# Connectors_ADC.net
KiCad netlist of a schematic drawn in Altium Designer
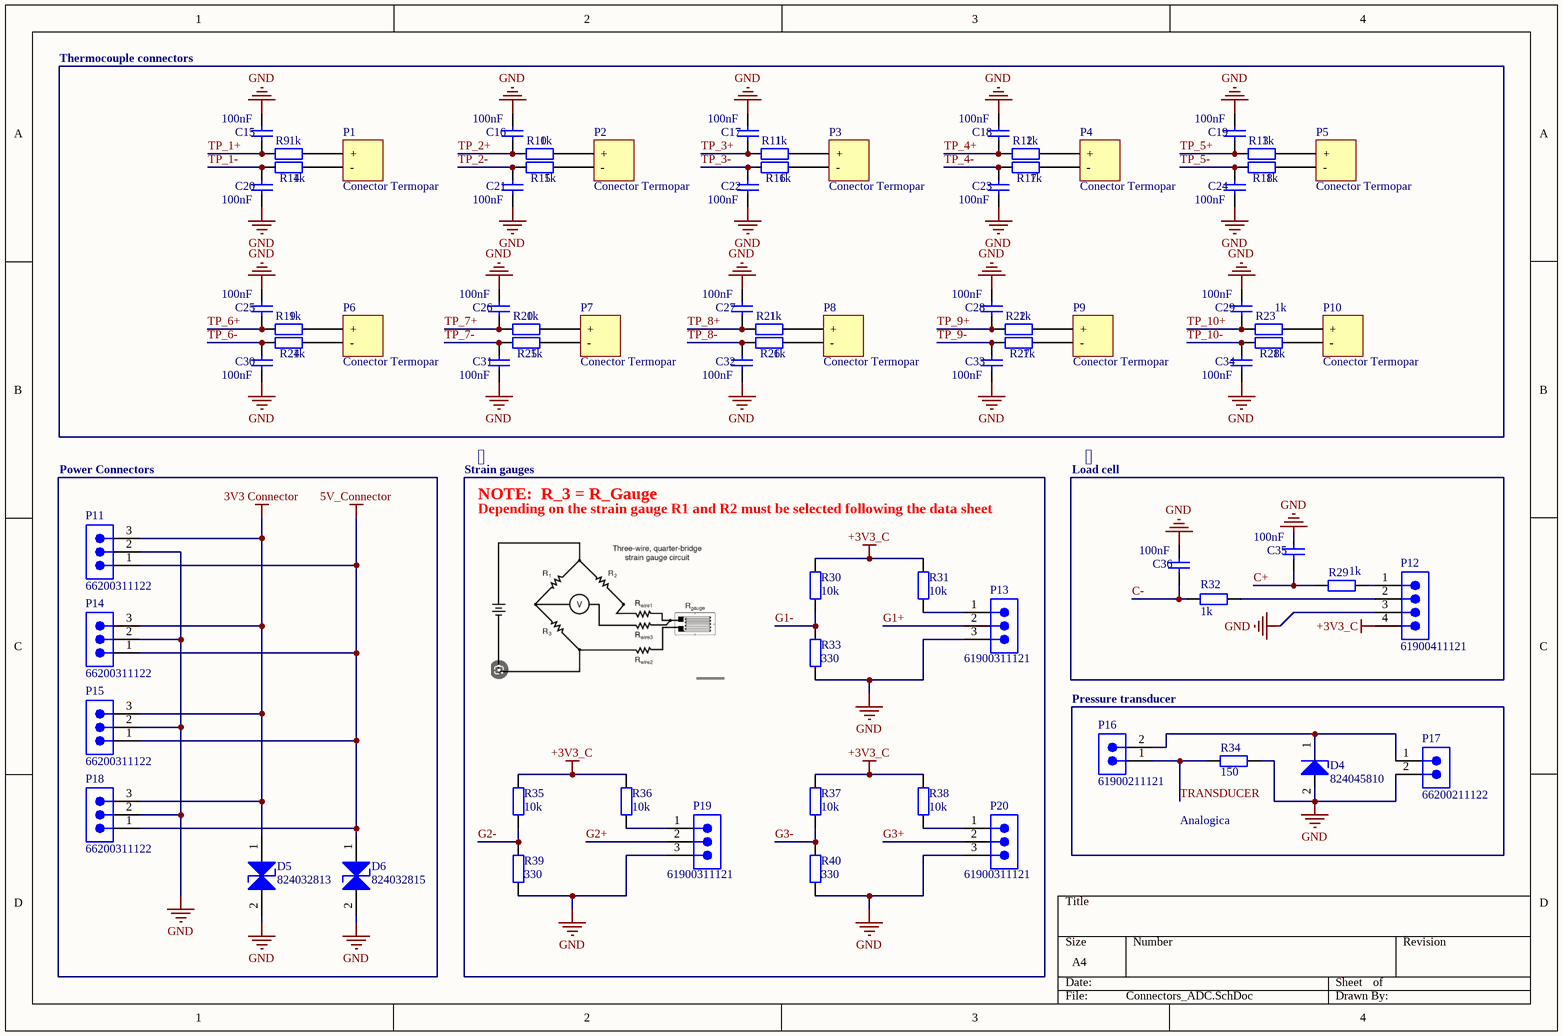
[diagram p0: Connectors_ADC.SchDoc]

(export (version "E")
  (design (tool "Eeschema 10.0.6"))
  (components
    (comp (ref "C15")
      (value "100nF")
      (footprint "WCAP-CSGP_0603_L1.6W0.8H0.8_Reflow")
      (description "WCAP-CSGP Multilayer Ceramic Chip Capacitor, General Purpose, size 0603, X7R, 100nF, 25VDC")
      (fields
        (field (name "MANUFACTURER") "Wurth Elektronik")
        (field (name "MANUFACTURER PART NUMBER") "885012206071")
      )
      (libsource (lib "LEEM UPM") (part "885012209047R"))
    )
    (comp (ref "C16")
      (value "100nF")
      (footprint "WCAP-CSGP_0603_L1.6W0.8H0.8_Reflow")
      (description "WCAP-CSGP Multilayer Ceramic Chip Capacitor, General Purpose, size 0603, X7R, 100nF, 25VDC")
      (fields
        (field (name "MANUFACTURER") "Wurth Elektronik")
        (field (name "MANUFACTURER PART NUMBER") "885012206071")
      )
      (libsource (lib "LEEM UPM") (part "885012209047R"))
    )
    (comp (ref "C17")
      (value "100nF")
      (footprint "WCAP-CSGP_0603_L1.6W0.8H0.8_Reflow")
      (description "WCAP-CSGP Multilayer Ceramic Chip Capacitor, General Purpose, size 0603, X7R, 100nF, 25VDC")
      (fields
        (field (name "MANUFACTURER") "Wurth Elektronik")
        (field (name "MANUFACTURER PART NUMBER") "885012206071")
      )
      (libsource (lib "LEEM UPM") (part "885012209047R"))
    )
    (comp (ref "C18")
      (value "100nF")
      (footprint "WCAP-CSGP_0603_L1.6W0.8H0.8_Reflow")
      (description "WCAP-CSGP Multilayer Ceramic Chip Capacitor, General Purpose, size 0603, X7R, 100nF, 25VDC")
      (fields
        (field (name "MANUFACTURER") "Wurth Elektronik")
        (field (name "MANUFACTURER PART NUMBER") "885012206071")
      )
      (libsource (lib "LEEM UPM") (part "885012209047R"))
    )
    (comp (ref "C19")
      (value "100nF")
      (footprint "WCAP-CSGP_0603_L1.6W0.8H0.8_Reflow")
      (description "WCAP-CSGP Multilayer Ceramic Chip Capacitor, General Purpose, size 0603, X7R, 100nF, 25VDC")
      (fields
        (field (name "MANUFACTURER") "Wurth Elektronik")
        (field (name "MANUFACTURER PART NUMBER") "885012206071")
      )
      (libsource (lib "LEEM UPM") (part "885012209047R"))
    )
    (comp (ref "C20")
      (value "100nF")
      (footprint "WCAP-CSGP_0603_L1.6W0.8H0.8_Reflow")
      (description "WCAP-CSGP Multilayer Ceramic Chip Capacitor, General Purpose, size 0603, X7R, 100nF, 25VDC")
      (fields
        (field (name "MANUFACTURER") "Wurth Elektronik")
        (field (name "MANUFACTURER PART NUMBER") "885012206071")
      )
      (libsource (lib "LEEM UPM") (part "885012209047R"))
    )
    (comp (ref "C21")
      (value "100nF")
      (footprint "WCAP-CSGP_0603_L1.6W0.8H0.8_Reflow")
      (description "WCAP-CSGP Multilayer Ceramic Chip Capacitor, General Purpose, size 0603, X7R, 100nF, 25VDC")
      (fields
        (field (name "MANUFACTURER") "Wurth Elektronik")
        (field (name "MANUFACTURER PART NUMBER") "885012206071")
      )
      (libsource (lib "LEEM UPM") (part "885012209047R"))
    )
    (comp (ref "C22")
      (value "100nF")
      (footprint "WCAP-CSGP_0603_L1.6W0.8H0.8_Reflow")
      (description "WCAP-CSGP Multilayer Ceramic Chip Capacitor, General Purpose, size 0603, X7R, 100nF, 25VDC")
      (fields
        (field (name "MANUFACTURER") "Wurth Elektronik")
        (field (name "MANUFACTURER PART NUMBER") "885012206071")
      )
      (libsource (lib "LEEM UPM") (part "885012209047R"))
    )
    (comp (ref "C23")
      (value "100nF")
      (footprint "WCAP-CSGP_0603_L1.6W0.8H0.8_Reflow")
      (description "WCAP-CSGP Multilayer Ceramic Chip Capacitor, General Purpose, size 0603, X7R, 100nF, 25VDC")
      (fields
        (field (name "MANUFACTURER") "Wurth Elektronik")
        (field (name "MANUFACTURER PART NUMBER") "885012206071")
      )
      (libsource (lib "LEEM UPM") (part "885012209047R"))
    )
    (comp (ref "C24")
      (value "100nF")
      (footprint "WCAP-CSGP_0603_L1.6W0.8H0.8_Reflow")
      (description "WCAP-CSGP Multilayer Ceramic Chip Capacitor, General Purpose, size 0603, X7R, 100nF, 25VDC")
      (fields
        (field (name "MANUFACTURER") "Wurth Elektronik")
        (field (name "MANUFACTURER PART NUMBER") "885012206071")
      )
      (libsource (lib "LEEM UPM") (part "885012209047R"))
    )
    (comp (ref "C25")
      (value "100nF")
      (footprint "WCAP-CSGP_0603_L1.6W0.8H0.8_Reflow")
      (description "WCAP-CSGP Multilayer Ceramic Chip Capacitor, General Purpose, size 0603, X7R, 100nF, 25VDC")
      (fields
        (field (name "MANUFACTURER") "Wurth Elektronik")
        (field (name "MANUFACTURER PART NUMBER") "885012206071")
      )
      (libsource (lib "LEEM UPM") (part "885012209047R"))
    )
    (comp (ref "C26")
      (value "100nF")
      (footprint "WCAP-CSGP_0603_L1.6W0.8H0.8_Reflow")
      (description "WCAP-CSGP Multilayer Ceramic Chip Capacitor, General Purpose, size 0603, X7R, 100nF, 25VDC")
      (fields
        (field (name "MANUFACTURER") "Wurth Elektronik")
        (field (name "MANUFACTURER PART NUMBER") "885012206071")
      )
      (libsource (lib "LEEM UPM") (part "885012209047R"))
    )
    (comp (ref "C27")
      (value "100nF")
      (footprint "WCAP-CSGP_0603_L1.6W0.8H0.8_Reflow")
      (description "WCAP-CSGP Multilayer Ceramic Chip Capacitor, General Purpose, size 0603, X7R, 100nF, 25VDC")
      (fields
        (field (name "MANUFACTURER") "Wurth Elektronik")
        (field (name "MANUFACTURER PART NUMBER") "885012206071")
      )
      (libsource (lib "LEEM UPM") (part "885012209047R"))
    )
    (comp (ref "C28")
      (value "100nF")
      (footprint "WCAP-CSGP_0603_L1.6W0.8H0.8_Reflow")
      (description "WCAP-CSGP Multilayer Ceramic Chip Capacitor, General Purpose, size 0603, X7R, 100nF, 25VDC")
      (fields
        (field (name "MANUFACTURER") "Wurth Elektronik")
        (field (name "MANUFACTURER PART NUMBER") "885012206071")
      )
      (libsource (lib "LEEM UPM") (part "885012209047R"))
    )
    (comp (ref "C29")
      (value "100nF")
      (footprint "WCAP-CSGP_0603_L1.6W0.8H0.8_Reflow")
      (description "WCAP-CSGP Multilayer Ceramic Chip Capacitor, General Purpose, size 0603, X7R, 100nF, 25VDC")
      (fields
        (field (name "MANUFACTURER") "Wurth Elektronik")
        (field (name "MANUFACTURER PART NUMBER") "885012206071")
      )
      (libsource (lib "LEEM UPM") (part "885012209047R"))
    )
    (comp (ref "C30")
      (value "100nF")
      (footprint "WCAP-CSGP_0603_L1.6W0.8H0.8_Reflow")
      (description "WCAP-CSGP Multilayer Ceramic Chip Capacitor, General Purpose, size 0603, X7R, 100nF, 25VDC")
      (fields
        (field (name "MANUFACTURER") "Wurth Elektronik")
        (field (name "MANUFACTURER PART NUMBER") "885012206071")
      )
      (libsource (lib "LEEM UPM") (part "885012209047R"))
    )
    (comp (ref "C31")
      (value "100nF")
      (footprint "WCAP-CSGP_0603_L1.6W0.8H0.8_Reflow")
      (description "WCAP-CSGP Multilayer Ceramic Chip Capacitor, General Purpose, size 0603, X7R, 100nF, 25VDC")
      (fields
        (field (name "MANUFACTURER") "Wurth Elektronik")
        (field (name "MANUFACTURER PART NUMBER") "885012206071")
      )
      (libsource (lib "LEEM UPM") (part "885012209047R"))
    )
    (comp (ref "C32")
      (value "100nF")
      (footprint "WCAP-CSGP_0603_L1.6W0.8H0.8_Reflow")
      (description "WCAP-CSGP Multilayer Ceramic Chip Capacitor, General Purpose, size 0603, X7R, 100nF, 25VDC")
      (fields
        (field (name "MANUFACTURER") "Wurth Elektronik")
        (field (name "MANUFACTURER PART NUMBER") "885012206071")
      )
      (libsource (lib "LEEM UPM") (part "885012209047R"))
    )
    (comp (ref "C33")
      (value "100nF")
      (footprint "WCAP-CSGP_0603_L1.6W0.8H0.8_Reflow")
      (description "WCAP-CSGP Multilayer Ceramic Chip Capacitor, General Purpose, size 0603, X7R, 100nF, 25VDC")
      (fields
        (field (name "MANUFACTURER") "Wurth Elektronik")
        (field (name "MANUFACTURER PART NUMBER") "885012206071")
      )
      (libsource (lib "LEEM UPM") (part "885012209047R"))
    )
    (comp (ref "C34")
      (value "100nF")
      (footprint "WCAP-CSGP_0603_L1.6W0.8H0.8_Reflow")
      (description "WCAP-CSGP Multilayer Ceramic Chip Capacitor, General Purpose, size 0603, X7R, 100nF, 25VDC")
      (fields
        (field (name "MANUFACTURER") "Wurth Elektronik")
        (field (name "MANUFACTURER PART NUMBER") "885012206071")
      )
      (libsource (lib "LEEM UPM") (part "885012209047R"))
    )
    (comp (ref "C35")
      (value "100nF")
      (footprint "WCAP-CSGP_0603_L1.6W0.8H0.8_Reflow")
      (description "WCAP-CSGP Multilayer Ceramic Chip Capacitor, General Purpose, size 0603, X7R, 100nF, 25VDC")
      (fields
        (field (name "MANUFACTURER") "Wurth Elektronik")
        (field (name "MANUFACTURER PART NUMBER") "885012206071")
      )
      (libsource (lib "LEEM UPM") (part "885012209047R"))
    )
    (comp (ref "C36")
      (value "100nF")
      (footprint "WCAP-CSGP_0603_L1.6W0.8H0.8_Reflow")
      (description "WCAP-CSGP Multilayer Ceramic Chip Capacitor, General Purpose, size 0603, X7R, 100nF, 25VDC")
      (fields
        (field (name "MANUFACTURER") "Wurth Elektronik")
        (field (name "MANUFACTURER PART NUMBER") "885012206071")
      )
      (libsource (lib "LEEM UPM") (part "885012209047R"))
    )
    (comp (ref "D4")
      (value "824045810")
      (footprint "WE-TVS_DFN1610-2L")
      (description "WE-TVS TVS Diode – Standard Series, DFN1610-2L, 1 Channel, 20V, 240pF")
      (fields (field (name "MANUFACTURER") "Wurth Elektronik"))
      (libsource (lib "LEEM UPM") (part "824045817"))
    )
    (comp (ref "D5")
      (value "824032813")
      (footprint "WE-TVS_DFN1610-2L")
      (description "824032813 Tvs Diode, Bidir, 3.3V, Dfn1610 Rohs Compliant: Yes")
      (libsource (lib "Altium Content Vault") (part "Diode_1 Channel_Bidirectional"))
    )
    (comp (ref "D6")
      (value "824032815")
      (footprint "WE-TVS_DFN1610-2L")
      (description "824032815 Tvs Diode, Bidir, 5V, Dfn1610 Rohs Compliant: Yes")
      (libsource (lib "Altium Content Vault") (part "Diode_1 Channel_Bidirectional"))
    )
    (comp (ref "P1")
      (value "Conector Termopar")
      (footprint "New footprint 1")
      (description "Conector para termopar vertical (hembra)")
      (libsource (lib "LEEM UPM") (part "TH"))
    )
    (comp (ref "P2")
      (value "Conector Termopar")
      (footprint "New footprint 1")
      (description "Conector para termopar vertical (hembra)")
      (libsource (lib "LEEM UPM") (part "TH"))
    )
    (comp (ref "P3")
      (value "Conector Termopar")
      (footprint "New footprint 1")
      (description "Conector para termopar vertical (hembra)")
      (libsource (lib "LEEM UPM") (part "TH"))
    )
    (comp (ref "P4")
      (value "Conector Termopar")
      (footprint "New footprint 1")
      (description "Conector para termopar vertical (hembra)")
      (libsource (lib "LEEM UPM") (part "TH"))
    )
    (comp (ref "P5")
      (value "Conector Termopar")
      (footprint "New footprint 1")
      (description "Conector para termopar vertical (hembra)")
      (libsource (lib "LEEM UPM") (part "TH"))
    )
    (comp (ref "P6")
      (value "Conector Termopar")
      (footprint "New footprint 1")
      (description "Conector para termopar vertical (hembra)")
      (libsource (lib "LEEM UPM") (part "TH"))
    )
    (comp (ref "P7")
      (value "Conector Termopar")
      (footprint "New footprint 1")
      (description "Conector para termopar vertical (hembra)")
      (libsource (lib "LEEM UPM") (part "TH"))
    )
    (comp (ref "P8")
      (value "Conector Termopar")
      (footprint "New footprint 1")
      (description "Conector para termopar vertical (hembra)")
      (libsource (lib "LEEM UPM") (part "TH"))
    )
    (comp (ref "P9")
      (value "Conector Termopar")
      (footprint "New footprint 1")
      (description "Conector para termopar vertical (hembra)")
      (libsource (lib "LEEM UPM") (part "TH"))
    )
    (comp (ref "P10")
      (value "Conector Termopar")
      (footprint "New footprint 1")
      (description "Conector para termopar vertical (hembra)")
      (libsource (lib "LEEM UPM") (part "TH"))
    )
    (comp (ref "P11")
      (value "66200311122")
      (footprint "66200311122")
      (description "WR-MPC3 THT Male Vertical Header, pitch 3mm, 3p")
      (fields (field (name "MANUFACTURER") "Wurth Elektronik"))
      (libsource (lib "LEEM UPM") (part "662303135922"))
    )
    (comp (ref "P12")
      (value "61900411121")
      (footprint "61900411121")
      (description "WR-WTB THT Male Vertical Locking Header, pitch 2.54mm, 4pins")
      (fields (field (name "MANUFACTURER") "Wurth Elektronik"))
      (libsource (lib "LEEM UPM") (part "679304124022"))
    )
    (comp (ref "P13")
      (value "61900311121")
      (footprint "61900311121")
      (description "WR-WTB THT Male Vertical Locking Header, pitch 2.54mm, 3pins")
      (fields (field (name "MANUFACTURER") "Wurth Elektronik"))
      (libsource (lib "LEEM UPM") (part "679303124022"))
    )
    (comp (ref "P14")
      (value "66200311122")
      (footprint "66200311122")
      (description "WR-MPC3 THT Male Vertical Header, pitch 3mm, 3p")
      (fields (field (name "MANUFACTURER") "Wurth Elektronik"))
      (libsource (lib "LEEM UPM") (part "662303135922"))
    )
    (comp (ref "P15")
      (value "66200311122")
      (footprint "66200311122")
      (description "WR-MPC3 THT Male Vertical Header, pitch 3mm, 3p")
      (fields (field (name "MANUFACTURER") "Wurth Elektronik"))
      (libsource (lib "LEEM UPM") (part "662303135922"))
    )
    (comp (ref "P16")
      (value "61900211121")
      (footprint "61900211121")
      (description "WR-WTB THT Male Vertical Locking Header, pitch 2.54mm, 2pins")
      (fields (field (name "MANUFACTURER") "Wurth Elektronik"))
      (libsource (lib "LEEM UPM") (part "679302124022"))
    )
    (comp (ref "P17")
      (value "66200211122")
      (footprint "66200211122")
      (description "WR-MPC3 THT Male Vertical Header, pitch 3mm, 2p")
      (fields (field (name "MANUFACTURER") "Wurth Elektronik"))
      (libsource (lib "LEEM UPM") (part "662302135922"))
    )
    (comp (ref "P18")
      (value "66200311122")
      (footprint "66200311122")
      (description "WR-MPC3 THT Male Vertical Header, pitch 3mm, 3p")
      (fields (field (name "MANUFACTURER") "Wurth Elektronik"))
      (libsource (lib "LEEM UPM") (part "662303135922"))
    )
    (comp (ref "P19")
      (value "61900311121")
      (footprint "61900311121")
      (description "WR-WTB THT Male Vertical Locking Header, pitch 2.54mm, 3pins")
      (fields (field (name "MANUFACTURER") "Wurth Elektronik"))
      (libsource (lib "LEEM UPM") (part "679303124022"))
    )
    (comp (ref "P20")
      (value "61900311121")
      (footprint "61900311121")
      (description "WR-WTB THT Male Vertical Locking Header, pitch 2.54mm, 3pins")
      (fields (field (name "MANUFACTURER") "Wurth Elektronik"))
      (libsource (lib "LEEM UPM") (part "679303124022"))
    )
    (comp (ref "R9")
      (value "1k")
      (footprint "WRIS-RSKS_0603_Reflow")
      (description "WRIS-RSKS Thick Film Resistor, size 0603, 1000Ohm, 100mW")
      (fields
        (field (name "MANUFACTURER PART NUMBER") "560112116014")
        (field (name "MANUFACTURER") "Wurth Elektronik")
      )
      (libsource (lib "LEEM UPM") (part "560112140010"))
    )
    (comp (ref "R10")
      (value "1k")
      (footprint "WRIS-RSKS_0603_Reflow")
      (description "WRIS-RSKS Thick Film Resistor, size 0603, 1000Ohm, 100mW")
      (fields
        (field (name "MANUFACTURER PART NUMBER") "560112116014")
        (field (name "MANUFACTURER") "Wurth Elektronik")
      )
      (libsource (lib "LEEM UPM") (part "560112140010"))
    )
    (comp (ref "R11")
      (value "1k")
      (footprint "WRIS-RSKS_0603_Reflow")
      (description "WRIS-RSKS Thick Film Resistor, size 0603, 1000Ohm, 100mW")
      (fields
        (field (name "MANUFACTURER PART NUMBER") "560112116014")
        (field (name "MANUFACTURER") "Wurth Elektronik")
      )
      (libsource (lib "LEEM UPM") (part "560112140010"))
    )
    (comp (ref "R12")
      (value "1k")
      (footprint "WRIS-RSKS_0603_Reflow")
      (description "WRIS-RSKS Thick Film Resistor, size 0603, 1000Ohm, 100mW")
      (fields
        (field (name "MANUFACTURER PART NUMBER") "560112116014")
        (field (name "MANUFACTURER") "Wurth Elektronik")
      )
      (libsource (lib "LEEM UPM") (part "560112140010"))
    )
    (comp (ref "R13")
      (value "1k")
      (footprint "WRIS-RSKS_0603_Reflow")
      (description "WRIS-RSKS Thick Film Resistor, size 0603, 1000Ohm, 100mW")
      (fields
        (field (name "MANUFACTURER PART NUMBER") "560112116014")
        (field (name "MANUFACTURER") "Wurth Elektronik")
      )
      (libsource (lib "LEEM UPM") (part "560112140010"))
    )
    (comp (ref "R14")
      (value "1k")
      (footprint "WRIS-RSKS_0603_Reflow")
      (description "WRIS-RSKS Thick Film Resistor, size 0603, 1000Ohm, 100mW")
      (fields
        (field (name "MANUFACTURER PART NUMBER") "560112116014")
        (field (name "MANUFACTURER") "Wurth Elektronik")
      )
      (libsource (lib "LEEM UPM") (part "560112140010"))
    )
    (comp (ref "R15")
      (value "1k")
      (footprint "WRIS-RSKS_0603_Reflow")
      (description "WRIS-RSKS Thick Film Resistor, size 0603, 1000Ohm, 100mW")
      (fields
        (field (name "MANUFACTURER PART NUMBER") "560112116014")
        (field (name "MANUFACTURER") "Wurth Elektronik")
      )
      (libsource (lib "LEEM UPM") (part "560112140010"))
    )
    (comp (ref "R16")
      (value "1k")
      (footprint "WRIS-RSKS_0603_Reflow")
      (description "WRIS-RSKS Thick Film Resistor, size 0603, 1000Ohm, 100mW")
      (fields
        (field (name "MANUFACTURER PART NUMBER") "560112116014")
        (field (name "MANUFACTURER") "Wurth Elektronik")
      )
      (libsource (lib "LEEM UPM") (part "560112140010"))
    )
    (comp (ref "R17")
      (value "1k")
      (footprint "WRIS-RSKS_0603_Reflow")
      (description "WRIS-RSKS Thick Film Resistor, size 0603, 1000Ohm, 100mW")
      (fields
        (field (name "MANUFACTURER PART NUMBER") "560112116014")
        (field (name "MANUFACTURER") "Wurth Elektronik")
      )
      (libsource (lib "LEEM UPM") (part "560112140010"))
    )
    (comp (ref "R18")
      (value "1k")
      (footprint "WRIS-RSKS_0603_Reflow")
      (description "WRIS-RSKS Thick Film Resistor, size 0603, 1000Ohm, 100mW")
      (fields
        (field (name "MANUFACTURER PART NUMBER") "560112116014")
        (field (name "MANUFACTURER") "Wurth Elektronik")
      )
      (libsource (lib "LEEM UPM") (part "560112140010"))
    )
    (comp (ref "R19")
      (value "1k")
      (footprint "WRIS-RSKS_0603_Reflow")
      (description "WRIS-RSKS Thick Film Resistor, size 0603, 1000Ohm, 100mW")
      (fields
        (field (name "MANUFACTURER PART NUMBER") "560112116014")
        (field (name "MANUFACTURER") "Wurth Elektronik")
      )
      (libsource (lib "LEEM UPM") (part "560112140010"))
    )
    (comp (ref "R20")
      (value "1k")
      (footprint "WRIS-RSKS_0603_Reflow")
      (description "WRIS-RSKS Thick Film Resistor, size 0603, 1000Ohm, 100mW")
      (fields
        (field (name "MANUFACTURER PART NUMBER") "560112116014")
        (field (name "MANUFACTURER") "Wurth Elektronik")
      )
      (libsource (lib "LEEM UPM") (part "560112140010"))
    )
    (comp (ref "R21")
      (value "1k")
      (footprint "WRIS-RSKS_0603_Reflow")
      (description "WRIS-RSKS Thick Film Resistor, size 0603, 1000Ohm, 100mW")
      (fields
        (field (name "MANUFACTURER PART NUMBER") "560112116014")
        (field (name "MANUFACTURER") "Wurth Elektronik")
      )
      (libsource (lib "LEEM UPM") (part "560112140010"))
    )
    (comp (ref "R22")
      (value "1k")
      (footprint "WRIS-RSKS_0603_Reflow")
      (description "WRIS-RSKS Thick Film Resistor, size 0603, 1000Ohm, 100mW")
      (fields
        (field (name "MANUFACTURER PART NUMBER") "560112116014")
        (field (name "MANUFACTURER") "Wurth Elektronik")
      )
      (libsource (lib "LEEM UPM") (part "560112140010"))
    )
    (comp (ref "R23")
      (value "1k")
      (footprint "WRIS-RSKS_0603_Reflow")
      (description "WRIS-RSKS Thick Film Resistor, size 0603, 1000Ohm, 100mW")
      (fields
        (field (name "MANUFACTURER PART NUMBER") "560112116014")
        (field (name "MANUFACTURER") "Wurth Elektronik")
      )
      (libsource (lib "LEEM UPM") (part "560112140010"))
    )
    (comp (ref "R24")
      (value "1k")
      (footprint "WRIS-RSKS_0603_Reflow")
      (description "WRIS-RSKS Thick Film Resistor, size 0603, 1000Ohm, 100mW")
      (fields
        (field (name "MANUFACTURER PART NUMBER") "560112116014")
        (field (name "MANUFACTURER") "Wurth Elektronik")
      )
      (libsource (lib "LEEM UPM") (part "560112140010"))
    )
    (comp (ref "R25")
      (value "1k")
      (footprint "WRIS-RSKS_0603_Reflow")
      (description "WRIS-RSKS Thick Film Resistor, size 0603, 1000Ohm, 100mW")
      (fields
        (field (name "MANUFACTURER PART NUMBER") "560112116014")
        (field (name "MANUFACTURER") "Wurth Elektronik")
      )
      (libsource (lib "LEEM UPM") (part "560112140010"))
    )
    (comp (ref "R26")
      (value "1k")
      (footprint "WRIS-RSKS_0603_Reflow")
      (description "WRIS-RSKS Thick Film Resistor, size 0603, 1000Ohm, 100mW")
      (fields
        (field (name "MANUFACTURER PART NUMBER") "560112116014")
        (field (name "MANUFACTURER") "Wurth Elektronik")
      )
      (libsource (lib "LEEM UPM") (part "560112140010"))
    )
    (comp (ref "R27")
      (value "1k")
      (footprint "WRIS-RSKS_0603_Reflow")
      (description "WRIS-RSKS Thick Film Resistor, size 0603, 1000Ohm, 100mW")
      (fields
        (field (name "MANUFACTURER PART NUMBER") "560112116014")
        (field (name "MANUFACTURER") "Wurth Elektronik")
      )
      (libsource (lib "LEEM UPM") (part "560112140010"))
    )
    (comp (ref "R28")
      (value "1k")
      (footprint "WRIS-RSKS_0603_Reflow")
      (description "WRIS-RSKS Thick Film Resistor, size 0603, 1000Ohm, 100mW")
      (fields
        (field (name "MANUFACTURER PART NUMBER") "560112116014")
        (field (name "MANUFACTURER") "Wurth Elektronik")
      )
      (libsource (lib "LEEM UPM") (part "560112140010"))
    )
    (comp (ref "R29")
      (value "1k")
      (footprint "WRIS-RSKS_0603_Reflow")
      (description "WRIS-RSKS Thick Film Resistor, size 0603, 1000Ohm, 100mW")
      (fields
        (field (name "MANUFACTURER PART NUMBER") "560112116014")
        (field (name "MANUFACTURER") "Wurth Elektronik")
      )
      (libsource (lib "LEEM UPM") (part "560112140010"))
    )
    (comp (ref "R30")
      (value "10k")
      (footprint "WRIS-RSKS_0603_Reflow")
      (description "WRIS-RSKS Thick Film Resistor, size 0603, 10000Ohm, 100mW")
      (fields
        (field (name "MANUFACTURER") "Wurth Elektronik")
        (field (name "MANUFACTURER PART NUMBER") "560112116005")
      )
      (libsource (lib "") (part "560112140010_1"))
    )
    (comp (ref "R31")
      (value "10k")
      (footprint "WRIS-RSKS_0603_Reflow")
      (description "WRIS-RSKS Thick Film Resistor, size 0603, 10000Ohm, 100mW")
      (fields
        (field (name "MANUFACTURER") "Wurth Elektronik")
        (field (name "MANUFACTURER PART NUMBER") "560112116005")
      )
      (libsource (lib "") (part "560112140010_1"))
    )
    (comp (ref "R32")
      (value "1k")
      (footprint "WRIS-RSKS_0603_Reflow")
      (description "WRIS-RSKS Thick Film Resistor, size 0603, 1000Ohm, 100mW")
      (fields
        (field (name "MANUFACTURER PART NUMBER") "560112116014")
        (field (name "MANUFACTURER") "Wurth Elektronik")
      )
      (libsource (lib "LEEM UPM") (part "560112140010"))
    )
    (comp (ref "R33")
      (value "330")
      (footprint "WRIS-RSKS_0603_Reflow")
      (description "WRIS-RSKS Thick Film Resistor, size 0603, 330Ohm, 100mW")
      (fields
        (field (name "MANUFACTURER") "Wurth Elektronik")
        (field (name "MANUFACTURER PART NUMBER") "560112116020")
      )
      (libsource (lib "") (part "560112140010_1"))
    )
    (comp (ref "R34")
      (value "150")
      (footprint "WRIS-RSKS_0603_Reflow")
      (description "WRIS-RSKS Thick Film Resistor, size 0603, 150Ohm, 100mW")
      (fields
        (field (name "MANUFACTURER") "Wurth Elektronik")
        (field (name "MANUFACTURER PART NUMBER") "560112116041")
      )
      (libsource (lib "") (part "560112140010_2"))
    )
    (comp (ref "R35")
      (value "10k")
      (footprint "WRIS-RSKS_0603_Reflow")
      (description "WRIS-RSKS Thick Film Resistor, size 0603, 10000Ohm, 100mW")
      (fields
        (field (name "MANUFACTURER") "Wurth Elektronik")
        (field (name "MANUFACTURER PART NUMBER") "560112116005")
      )
      (libsource (lib "") (part "560112140010_1"))
    )
    (comp (ref "R36")
      (value "10k")
      (footprint "WRIS-RSKS_0603_Reflow")
      (description "WRIS-RSKS Thick Film Resistor, size 0603, 10000Ohm, 100mW")
      (fields
        (field (name "MANUFACTURER") "Wurth Elektronik")
        (field (name "MANUFACTURER PART NUMBER") "560112116005")
      )
      (libsource (lib "") (part "560112140010_1"))
    )
    (comp (ref "R37")
      (value "10k")
      (footprint "WRIS-RSKS_0603_Reflow")
      (description "WRIS-RSKS Thick Film Resistor, size 0603, 10000Ohm, 100mW")
      (fields
        (field (name "MANUFACTURER") "Wurth Elektronik")
        (field (name "MANUFACTURER PART NUMBER") "560112116005")
      )
      (libsource (lib "") (part "560112140010_1"))
    )
    (comp (ref "R38")
      (value "10k")
      (footprint "WRIS-RSKS_0603_Reflow")
      (description "WRIS-RSKS Thick Film Resistor, size 0603, 10000Ohm, 100mW")
      (fields
        (field (name "MANUFACTURER") "Wurth Elektronik")
        (field (name "MANUFACTURER PART NUMBER") "560112116005")
      )
      (libsource (lib "") (part "560112140010_1"))
    )
    (comp (ref "R39")
      (value "330")
      (footprint "WRIS-RSKS_0603_Reflow")
      (description "WRIS-RSKS Thick Film Resistor, size 0603, 330Ohm, 100mW")
      (fields
        (field (name "MANUFACTURER") "Wurth Elektronik")
        (field (name "MANUFACTURER PART NUMBER") "560112116020")
      )
      (libsource (lib "") (part "560112140010_1"))
    )
    (comp (ref "R40")
      (value "330")
      (footprint "WRIS-RSKS_0603_Reflow")
      (description "WRIS-RSKS Thick Film Resistor, size 0603, 330Ohm, 100mW")
      (fields
        (field (name "MANUFACTURER") "Wurth Elektronik")
        (field (name "MANUFACTURER PART NUMBER") "560112116020")
      )
      (libsource (lib "") (part "560112140010_1"))
    )
  )
  (nets
    (net (code "1") (name "+3V3_C") (class "Default")
      (node (ref "P12") (pin "4") (pinfunction "4_4") (pintype "passive"))
      (node (ref "R30") (pin "2") (pinfunction "2_2") (pintype "passive"))
      (node (ref "R31") (pin "2") (pinfunction "2_2") (pintype "passive"))
      (node (ref "R35") (pin "2") (pinfunction "2_2") (pintype "passive"))
      (node (ref "R36") (pin "2") (pinfunction "2_2") (pintype "passive"))
      (node (ref "R37") (pin "2") (pinfunction "2_2") (pintype "passive"))
      (node (ref "R38") (pin "2") (pinfunction "2_2") (pintype "passive"))
    )
    (net (code "2") (name "/C+") (class "Default")
      (node (ref "C35") (pin "1") (pinfunction "1_1") (pintype "passive"))
      (node (ref "R29") (pin "1") (pinfunction "1_1") (pintype "passive"))
    )
    (net (code "3") (name "/C-") (class "Default")
      (node (ref "C36") (pin "1") (pinfunction "1_1") (pintype "passive"))
      (node (ref "R32") (pin "1") (pinfunction "1_1") (pintype "passive"))
    )
    (net (code "4") (name "/G1+") (class "Default")
      (node (ref "P13") (pin "2") (pinfunction "2_2") (pintype "passive"))
    )
    (net (code "5") (name "/G1-") (class "Default")
      (node (ref "R30") (pin "1") (pinfunction "1_1") (pintype "passive"))
      (node (ref "R33") (pin "2") (pinfunction "2_2") (pintype "passive"))
    )
    (net (code "6") (name "/G2+") (class "Default")
      (node (ref "P19") (pin "2") (pinfunction "2_2") (pintype "passive"))
    )
    (net (code "7") (name "/G2-") (class "Default")
      (node (ref "R35") (pin "1") (pinfunction "1_1") (pintype "passive"))
      (node (ref "R39") (pin "2") (pinfunction "2_2") (pintype "passive"))
    )
    (net (code "8") (name "/G3+") (class "Default")
      (node (ref "P20") (pin "2") (pinfunction "2_2") (pintype "passive"))
    )
    (net (code "9") (name "/G3-") (class "Default")
      (node (ref "R37") (pin "1") (pinfunction "1_1") (pintype "passive"))
      (node (ref "R40") (pin "2") (pinfunction "2_2") (pintype "passive"))
    )
    (net (code "10") (name "/TP_1+") (class "Default")
      (node (ref "C15") (pin "1") (pinfunction "1_1") (pintype "passive"))
      (node (ref "R9") (pin "1") (pinfunction "1_1") (pintype "passive"))
    )
    (net (code "11") (name "/TP_1-") (class "Default")
      (node (ref "C20") (pin "2") (pinfunction "2_2") (pintype "passive"))
      (node (ref "R14") (pin "1") (pinfunction "1_1") (pintype "passive"))
    )
    (net (code "12") (name "/TP_2+") (class "Default")
      (node (ref "C16") (pin "1") (pinfunction "1_1") (pintype "passive"))
      (node (ref "R10") (pin "1") (pinfunction "1_1") (pintype "passive"))
    )
    (net (code "13") (name "/TP_2-") (class "Default")
      (node (ref "C21") (pin "2") (pinfunction "2_2") (pintype "passive"))
      (node (ref "R15") (pin "1") (pinfunction "1_1") (pintype "passive"))
    )
    (net (code "14") (name "/TP_3+") (class "Default")
      (node (ref "C17") (pin "1") (pinfunction "1_1") (pintype "passive"))
      (node (ref "R11") (pin "1") (pinfunction "1_1") (pintype "passive"))
    )
    (net (code "15") (name "/TP_3-") (class "Default")
      (node (ref "C22") (pin "2") (pinfunction "2_2") (pintype "passive"))
      (node (ref "R16") (pin "1") (pinfunction "1_1") (pintype "passive"))
    )
    (net (code "16") (name "/TP_4+") (class "Default")
      (node (ref "C18") (pin "1") (pinfunction "1_1") (pintype "passive"))
      (node (ref "R12") (pin "1") (pinfunction "1_1") (pintype "passive"))
    )
    (net (code "17") (name "/TP_4-") (class "Default")
      (node (ref "C23") (pin "2") (pinfunction "2_2") (pintype "passive"))
      (node (ref "R17") (pin "1") (pinfunction "1_1") (pintype "passive"))
    )
    (net (code "18") (name "/TP_5+") (class "Default")
      (node (ref "C19") (pin "1") (pinfunction "1_1") (pintype "passive"))
      (node (ref "R13") (pin "1") (pinfunction "1_1") (pintype "passive"))
    )
    (net (code "19") (name "/TP_5-") (class "Default")
      (node (ref "C24") (pin "2") (pinfunction "2_2") (pintype "passive"))
      (node (ref "R18") (pin "1") (pinfunction "1_1") (pintype "passive"))
    )
    (net (code "20") (name "/TP_6+") (class "Default")
      (node (ref "C25") (pin "1") (pinfunction "1_1") (pintype "passive"))
      (node (ref "R19") (pin "1") (pinfunction "1_1") (pintype "passive"))
    )
    (net (code "21") (name "/TP_6-") (class "Default")
      (node (ref "C30") (pin "2") (pinfunction "2_2") (pintype "passive"))
      (node (ref "R24") (pin "1") (pinfunction "1_1") (pintype "passive"))
    )
    (net (code "22") (name "/TP_7+") (class "Default")
      (node (ref "C26") (pin "1") (pinfunction "1_1") (pintype "passive"))
      (node (ref "R20") (pin "1") (pinfunction "1_1") (pintype "passive"))
    )
    (net (code "23") (name "/TP_7-") (class "Default")
      (node (ref "C31") (pin "2") (pinfunction "2_2") (pintype "passive"))
      (node (ref "R25") (pin "1") (pinfunction "1_1") (pintype "passive"))
    )
    (net (code "24") (name "/TP_8+") (class "Default")
      (node (ref "C27") (pin "1") (pinfunction "1_1") (pintype "passive"))
      (node (ref "R21") (pin "1") (pinfunction "1_1") (pintype "passive"))
    )
    (net (code "25") (name "/TP_8-") (class "Default")
      (node (ref "C32") (pin "2") (pinfunction "2_2") (pintype "passive"))
      (node (ref "R26") (pin "1") (pinfunction "1_1") (pintype "passive"))
    )
    (net (code "26") (name "/TP_9+") (class "Default")
      (node (ref "C28") (pin "1") (pinfunction "1_1") (pintype "passive"))
      (node (ref "R22") (pin "1") (pinfunction "1_1") (pintype "passive"))
    )
    (net (code "27") (name "/TP_9-") (class "Default")
      (node (ref "C33") (pin "2") (pinfunction "2_2") (pintype "passive"))
      (node (ref "R27") (pin "1") (pinfunction "1_1") (pintype "passive"))
    )
    (net (code "28") (name "/TP_10+") (class "Default")
      (node (ref "C29") (pin "1") (pinfunction "1_1") (pintype "passive"))
      (node (ref "R23") (pin "1") (pinfunction "1_1") (pintype "passive"))
    )
    (net (code "29") (name "/TP_10-") (class "Default")
      (node (ref "C34") (pin "2") (pinfunction "2_2") (pintype "passive"))
      (node (ref "R28") (pin "1") (pinfunction "1_1") (pintype "passive"))
    )
    (net (code "30") (name "/TRANSDUCER") (class "Default")
      (node (ref "P16") (pin "1") (pinfunction "1_1") (pintype "passive"))
      (node (ref "R34") (pin "2") (pinfunction "2_2") (pintype "passive"))
    )
    (net (code "31") (name "3V3 Connector") (class "Default")
      (node (ref "D5") (pin "1") (pinfunction "I/O_1_1") (pintype "passive"))
      (node (ref "P11") (pin "3") (pinfunction "3_3") (pintype "passive"))
      (node (ref "P14") (pin "3") (pinfunction "3_3") (pintype "passive"))
      (node (ref "P15") (pin "3") (pinfunction "3_3") (pintype "passive"))
      (node (ref "P18") (pin "3") (pinfunction "3_3") (pintype "passive"))
    )
    (net (code "32") (name "5V_Connector") (class "Default")
      (node (ref "D6") (pin "1") (pinfunction "I/O_1_1") (pintype "passive"))
      (node (ref "P11") (pin "1") (pinfunction "1_1") (pintype "passive"))
      (node (ref "P14") (pin "1") (pinfunction "1_1") (pintype "passive"))
      (node (ref "P15") (pin "1") (pinfunction "1_1") (pintype "passive"))
      (node (ref "P18") (pin "1") (pinfunction "1_1") (pintype "passive"))
    )
    (net (code "33") (name "GND") (class "Default")
      (node (ref "C15") (pin "2") (pinfunction "2_2") (pintype "passive"))
      (node (ref "C16") (pin "2") (pinfunction "2_2") (pintype "passive"))
      (node (ref "C17") (pin "2") (pinfunction "2_2") (pintype "passive"))
      (node (ref "C18") (pin "2") (pinfunction "2_2") (pintype "passive"))
      (node (ref "C19") (pin "2") (pinfunction "2_2") (pintype "passive"))
      (node (ref "C20") (pin "1") (pinfunction "1_1") (pintype "passive"))
      (node (ref "C21") (pin "1") (pinfunction "1_1") (pintype "passive"))
      (node (ref "C22") (pin "1") (pinfunction "1_1") (pintype "passive"))
      (node (ref "C23") (pin "1") (pinfunction "1_1") (pintype "passive"))
      (node (ref "C24") (pin "1") (pinfunction "1_1") (pintype "passive"))
      (node (ref "C25") (pin "2") (pinfunction "2_2") (pintype "passive"))
      (node (ref "C26") (pin "2") (pinfunction "2_2") (pintype "passive"))
      (node (ref "C27") (pin "2") (pinfunction "2_2") (pintype "passive"))
      (node (ref "C28") (pin "2") (pinfunction "2_2") (pintype "passive"))
      (node (ref "C29") (pin "2") (pinfunction "2_2") (pintype "passive"))
      (node (ref "C30") (pin "1") (pinfunction "1_1") (pintype "passive"))
      (node (ref "C31") (pin "1") (pinfunction "1_1") (pintype "passive"))
      (node (ref "C32") (pin "1") (pinfunction "1_1") (pintype "passive"))
      (node (ref "C33") (pin "1") (pinfunction "1_1") (pintype "passive"))
      (node (ref "C34") (pin "1") (pinfunction "1_1") (pintype "passive"))
      (node (ref "C35") (pin "2") (pinfunction "2_2") (pintype "passive"))
      (node (ref "C36") (pin "2") (pinfunction "2_2") (pintype "passive"))
      (node (ref "D4") (pin "2") (pinfunction "GND_2") (pintype "passive"))
      (node (ref "D5") (pin "2") (pinfunction "GND_2") (pintype "passive"))
      (node (ref "D6") (pin "2") (pinfunction "GND_2") (pintype "passive"))
      (node (ref "P11") (pin "2") (pinfunction "2_2") (pintype "passive"))
      (node (ref "P12") (pin "3") (pinfunction "3_3") (pintype "passive"))
      (node (ref "P13") (pin "3") (pinfunction "3_3") (pintype "passive"))
      (node (ref "P14") (pin "2") (pinfunction "2_2") (pintype "passive"))
      (node (ref "P15") (pin "2") (pinfunction "2_2") (pintype "passive"))
      (node (ref "P17") (pin "2") (pinfunction "2_2") (pintype "passive"))
      (node (ref "P18") (pin "2") (pinfunction "2_2") (pintype "passive"))
      (node (ref "P19") (pin "3") (pinfunction "3_3") (pintype "passive"))
      (node (ref "P20") (pin "3") (pinfunction "3_3") (pintype "passive"))
      (node (ref "R33") (pin "1") (pinfunction "1_1") (pintype "passive"))
      (node (ref "R34") (pin "1") (pinfunction "1_1") (pintype "passive"))
      (node (ref "R39") (pin "1") (pinfunction "1_1") (pintype "passive"))
      (node (ref "R40") (pin "1") (pinfunction "1_1") (pintype "passive"))
    )
    (net (code "34") (name "Net-(D4-I{slash}O_1)") (class "Default")
      (node (ref "D4") (pin "1") (pinfunction "I/O_1_1") (pintype "passive"))
      (node (ref "P16") (pin "2") (pinfunction "2_2") (pintype "passive"))
      (node (ref "P17") (pin "1") (pinfunction "1_1") (pintype "passive"))
    )
    (net (code "35") (name "Net-(P1-+)") (class "Default")
      (node (ref "P1") (pin "1") (pinfunction "+_1") (pintype "passive"))
      (node (ref "R9") (pin "2") (pinfunction "2_2") (pintype "passive"))
    )
    (net (code "36") (name "Net-(P1--)") (class "Default")
      (node (ref "P1") (pin "2") (pinfunction "-_2") (pintype "passive"))
      (node (ref "R14") (pin "2") (pinfunction "2_2") (pintype "passive"))
    )
    (net (code "37") (name "Net-(P2-+)") (class "Default")
      (node (ref "P2") (pin "1") (pinfunction "+_1") (pintype "passive"))
      (node (ref "R10") (pin "2") (pinfunction "2_2") (pintype "passive"))
    )
    (net (code "38") (name "Net-(P2--)") (class "Default")
      (node (ref "P2") (pin "2") (pinfunction "-_2") (pintype "passive"))
      (node (ref "R15") (pin "2") (pinfunction "2_2") (pintype "passive"))
    )
    (net (code "39") (name "Net-(P3-+)") (class "Default")
      (node (ref "P3") (pin "1") (pinfunction "+_1") (pintype "passive"))
      (node (ref "R11") (pin "2") (pinfunction "2_2") (pintype "passive"))
    )
    (net (code "40") (name "Net-(P3--)") (class "Default")
      (node (ref "P3") (pin "2") (pinfunction "-_2") (pintype "passive"))
      (node (ref "R16") (pin "2") (pinfunction "2_2") (pintype "passive"))
    )
    (net (code "41") (name "Net-(P4-+)") (class "Default")
      (node (ref "P4") (pin "1") (pinfunction "+_1") (pintype "passive"))
      (node (ref "R12") (pin "2") (pinfunction "2_2") (pintype "passive"))
    )
    (net (code "42") (name "Net-(P4--)") (class "Default")
      (node (ref "P4") (pin "2") (pinfunction "-_2") (pintype "passive"))
      (node (ref "R17") (pin "2") (pinfunction "2_2") (pintype "passive"))
    )
    (net (code "43") (name "Net-(P5-+)") (class "Default")
      (node (ref "P5") (pin "1") (pinfunction "+_1") (pintype "passive"))
      (node (ref "R13") (pin "2") (pinfunction "2_2") (pintype "passive"))
    )
    (net (code "44") (name "Net-(P5--)") (class "Default")
      (node (ref "P5") (pin "2") (pinfunction "-_2") (pintype "passive"))
      (node (ref "R18") (pin "2") (pinfunction "2_2") (pintype "passive"))
    )
    (net (code "45") (name "Net-(P6-+)") (class "Default")
      (node (ref "P6") (pin "1") (pinfunction "+_1") (pintype "passive"))
      (node (ref "R19") (pin "2") (pinfunction "2_2") (pintype "passive"))
    )
    (net (code "46") (name "Net-(P6--)") (class "Default")
      (node (ref "P6") (pin "2") (pinfunction "-_2") (pintype "passive"))
      (node (ref "R24") (pin "2") (pinfunction "2_2") (pintype "passive"))
    )
    (net (code "47") (name "Net-(P7-+)") (class "Default")
      (node (ref "P7") (pin "1") (pinfunction "+_1") (pintype "passive"))
      (node (ref "R20") (pin "2") (pinfunction "2_2") (pintype "passive"))
    )
    (net (code "48") (name "Net-(P7--)") (class "Default")
      (node (ref "P7") (pin "2") (pinfunction "-_2") (pintype "passive"))
      (node (ref "R25") (pin "2") (pinfunction "2_2") (pintype "passive"))
    )
    (net (code "49") (name "Net-(P8-+)") (class "Default")
      (node (ref "P8") (pin "1") (pinfunction "+_1") (pintype "passive"))
      (node (ref "R21") (pin "2") (pinfunction "2_2") (pintype "passive"))
    )
    (net (code "50") (name "Net-(P8--)") (class "Default")
      (node (ref "P8") (pin "2") (pinfunction "-_2") (pintype "passive"))
      (node (ref "R26") (pin "2") (pinfunction "2_2") (pintype "passive"))
    )
    (net (code "51") (name "Net-(P9-+)") (class "Default")
      (node (ref "P9") (pin "1") (pinfunction "+_1") (pintype "passive"))
      (node (ref "R22") (pin "2") (pinfunction "2_2") (pintype "passive"))
    )
    (net (code "52") (name "Net-(P9--)") (class "Default")
      (node (ref "P9") (pin "2") (pinfunction "-_2") (pintype "passive"))
      (node (ref "R27") (pin "2") (pinfunction "2_2") (pintype "passive"))
    )
    (net (code "53") (name "Net-(P10-+)") (class "Default")
      (node (ref "P10") (pin "1") (pinfunction "+_1") (pintype "passive"))
      (node (ref "R23") (pin "2") (pinfunction "2_2") (pintype "passive"))
    )
    (net (code "54") (name "Net-(P10--)") (class "Default")
      (node (ref "P10") (pin "2") (pinfunction "-_2") (pintype "passive"))
      (node (ref "R28") (pin "2") (pinfunction "2_2") (pintype "passive"))
    )
    (net (code "55") (name "Net-(P12-Pad1)") (class "Default")
      (node (ref "P12") (pin "1") (pinfunction "1_1") (pintype "passive"))
      (node (ref "R29") (pin "2") (pinfunction "2_2") (pintype "passive"))
    )
    (net (code "56") (name "Net-(P12-Pad2)") (class "Default")
      (node (ref "P12") (pin "2") (pinfunction "2_2") (pintype "passive"))
      (node (ref "R32") (pin "2") (pinfunction "2_2") (pintype "passive"))
    )
    (net (code "57") (name "Net-(P13-Pad1)") (class "Default")
      (node (ref "P13") (pin "1") (pinfunction "1_1") (pintype "passive"))
      (node (ref "R31") (pin "1") (pinfunction "1_1") (pintype "passive"))
    )
    (net (code "58") (name "Net-(P19-Pad1)") (class "Default")
      (node (ref "P19") (pin "1") (pinfunction "1_1") (pintype "passive"))
      (node (ref "R36") (pin "1") (pinfunction "1_1") (pintype "passive"))
    )
    (net (code "59") (name "Net-(P20-Pad1)") (class "Default")
      (node (ref "P20") (pin "1") (pinfunction "1_1") (pintype "passive"))
      (node (ref "R38") (pin "1") (pinfunction "1_1") (pintype "passive"))
    )
  )
)
